# 07_V5_PWM_IO.net
KiCad netlist of a schematic drawn in Altium Designer
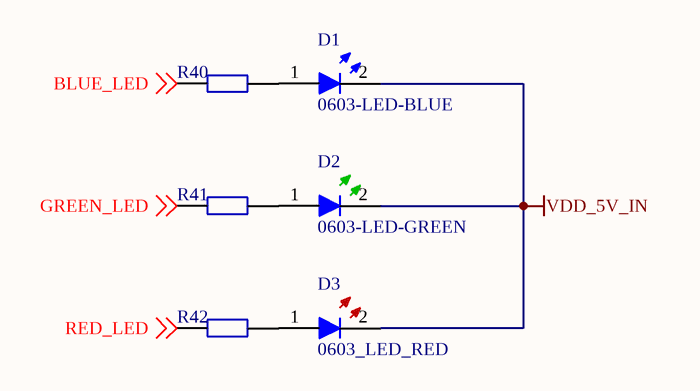
[diagram p0: 07_V5_PWM_IO.SchDoc]

(export (version "E")
  (design (tool "Eeschema 10.0.6"))
  (components
    (comp (ref "D1")
      (value "0603-LED-BLUE")
      (footprint "0603-LED-blue")
      (libsource (lib "CUAV") (part "0603-LED-BLUE"))
    )
    (comp (ref "D2")
      (value "0603-LED-GREEN")
      (footprint "0603-LED-Green")
      (libsource (lib "CUAV") (part "0603-LED-GREEN"))
    )
    (comp (ref "D3")
      (value "0603_LED_RED")
      (footprint "0603-LED-RED")
      (libsource (lib "CUAV") (part "0603_LED_RED"))
    )
    (comp (ref "R40")
      (value "1K")
      (footprint "0402R")
      (description "0402R100R 1%")
      (libsource (lib "CUAV") (part "0402R100R"))
    )
    (comp (ref "R41")
      (value "1K")
      (footprint "0402R")
      (description "0402R100R 1%")
      (libsource (lib "CUAV") (part "0402R100R"))
    )
    (comp (ref "R42")
      (value "1K")
      (footprint "0402R")
      (description "0402R100R 1%")
      (libsource (lib "CUAV") (part "0402R100R"))
    )
  )
  (nets
    (net (code "1") (name "BLUE_LED") (class "Default") (node (ref "R40") (pin "1") (pintype "passive")))
    (net (code "2") (name "GREEN_LED") (class "Default") (node (ref "R41") (pin "1") (pintype "passive")))
    (net (code "3") (name "Net-(D1-Pad1)") (class "Default")
      (node (ref "D1") (pin "1") (pintype "passive"))
      (node (ref "R40") (pin "2") (pintype "passive"))
    )
    (net (code "4") (name "Net-(D2-Pad1)") (class "Default")
      (node (ref "D2") (pin "1") (pintype "passive"))
      (node (ref "R41") (pin "2") (pintype "passive"))
    )
    (net (code "5") (name "Net-(D3-Pad1)") (class "Default")
      (node (ref "D3") (pin "1") (pintype "passive"))
      (node (ref "R42") (pin "2") (pintype "passive"))
    )
    (net (code "6") (name "RED_LED") (class "Default") (node (ref "R42") (pin "1") (pintype "passive")))
    (net (code "7") (name "VDD_5V_IN") (class "Default")
      (node (ref "D1") (pin "2") (pintype "passive"))
      (node (ref "D2") (pin "2") (pintype "passive"))
      (node (ref "D3") (pin "2") (pintype "passive"))
    )
  )
)
